# SparkFun_Transceiver_Breakout_NRF24LU1.net
KiCad netlist of a schematic drawn in EAGLE
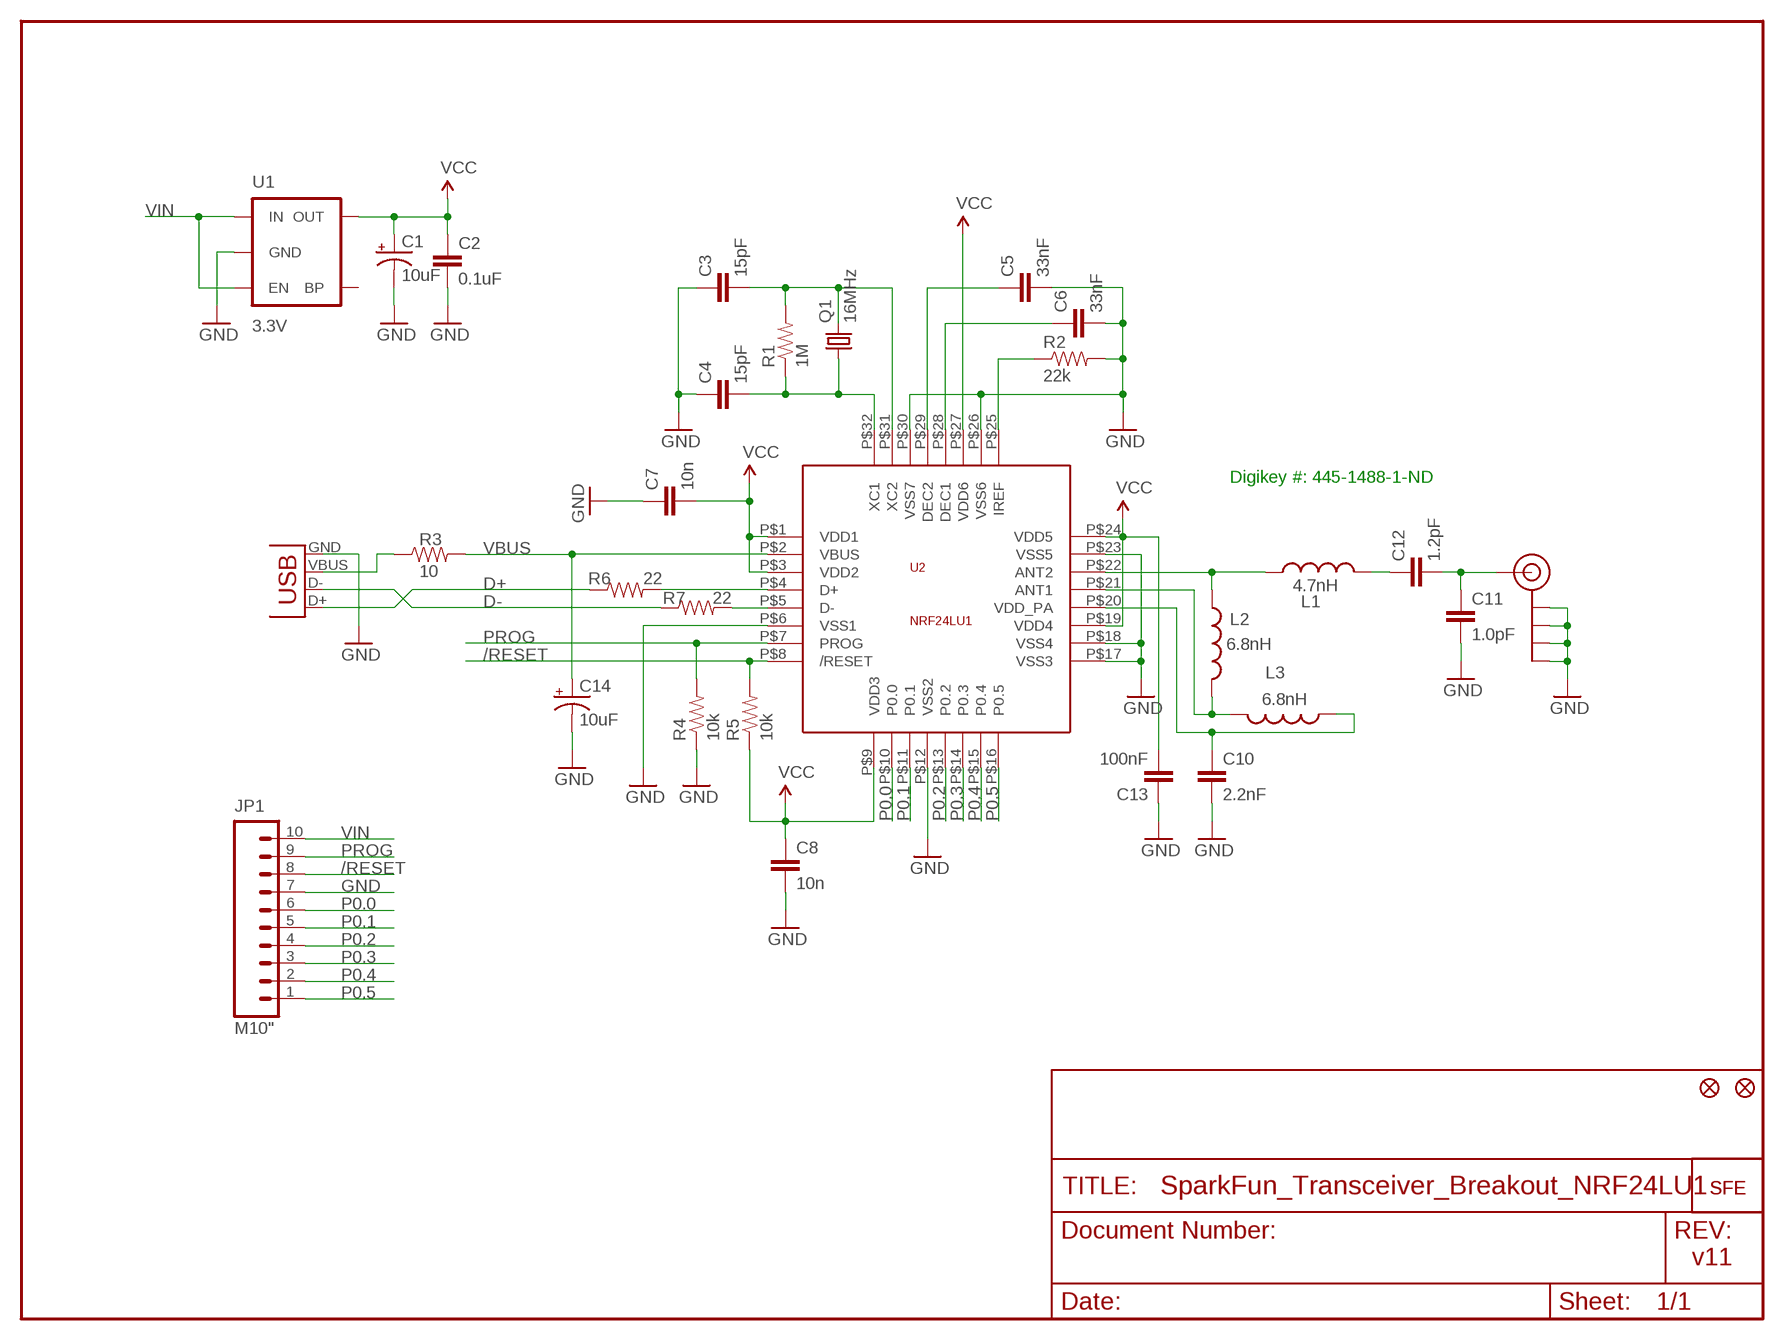
[diagram p0: schematic, sheet 1]

(export (version "E")
  (design (tool "Eeschema 10.0.6"))
  (components
    (comp (ref "C1")
      (value "10uF")
      (footprint "eagle-import:EIA3216")
      (libsource (lib "eagle-import") (part "CAP_POL1206"))
    )
    (comp (ref "C2")
      (value "0.1uF")
      (footprint "eagle-import:0402-CAP")
      (libsource (lib "eagle-import") (part "CAP0402-CAP"))
    )
    (comp (ref "C3")
      (value "15pF")
      (footprint "eagle-import:0402-CAP")
      (libsource (lib "eagle-import") (part "CAP0402-CAP"))
    )
    (comp (ref "C4")
      (value "15pF")
      (footprint "eagle-import:0402-CAP")
      (libsource (lib "eagle-import") (part "CAP0402-CAP"))
    )
    (comp (ref "C5")
      (value "33nF")
      (footprint "eagle-import:0402-CAP")
      (libsource (lib "eagle-import") (part "CAP0402-CAP"))
    )
    (comp (ref "C6")
      (value "33nF")
      (footprint "eagle-import:0402-CAP")
      (libsource (lib "eagle-import") (part "CAP0402-CAP"))
    )
    (comp (ref "C7")
      (value "10n")
      (footprint "eagle-import:0402-CAP")
      (libsource (lib "eagle-import") (part "CAP0402-CAP"))
    )
    (comp (ref "C8")
      (value "10n")
      (footprint "eagle-import:0402-CAP")
      (libsource (lib "eagle-import") (part "CAP0402-CAP"))
    )
    (comp (ref "C10")
      (value "2.2nF")
      (footprint "eagle-import:0402-CAP")
      (libsource (lib "eagle-import") (part "CAP0402-CAP"))
    )
    (comp (ref "C11")
      (value "1.0pF")
      (footprint "eagle-import:0402-CAP")
      (libsource (lib "eagle-import") (part "CAP0402-CAP"))
    )
    (comp (ref "C12")
      (value "1.2pF")
      (footprint "eagle-import:0402-CAP")
      (libsource (lib "eagle-import") (part "CAP0402-CAP"))
    )
    (comp (ref "C13")
      (value "100nF")
      (footprint "eagle-import:0402-CAP")
      (libsource (lib "eagle-import") (part "CAP0402-CAP"))
    )
    (comp (ref "C14")
      (value "10uF")
      (footprint "eagle-import:EIA3216")
      (libsource (lib "eagle-import") (part "CAP_POL1206"))
    )
    (comp (ref "J$1")
      (value "SMA_EDGE")
      (footprint "eagle-import:SMA-EDGE")
      (libsource (lib "eagle-import") (part "SMA_EDGE"))
    )
    (comp (ref "JP1")
      (value "M10\"")
      (footprint "eagle-import:1X10")
      (libsource (lib "eagle-import") (part "M10{dblquote}"))
    )
    (comp (ref "JP2")
      (value "LOGO-SFENEW")
      (footprint "eagle-import:SFE-NEW-WEBLOGO")
      (libsource (lib "eagle-import") (part "LOGO-SFENEW"))
    )
    (comp (ref "L1")
      (value "4.7nH")
      (footprint "eagle-import:C0402")
      (libsource (lib "eagle-import") (part "INDUCTOR0402"))
    )
    (comp (ref "L2")
      (value "6.8nH")
      (footprint "eagle-import:C0402")
      (libsource (lib "eagle-import") (part "INDUCTOR0402"))
    )
    (comp (ref "L3")
      (value "6.8nH")
      (footprint "eagle-import:C0402")
      (libsource (lib "eagle-import") (part "INDUCTOR0402"))
    )
    (comp (ref "Q1")
      (value "16MHz")
      (footprint "eagle-import:CRYSTAL-SMD-5X3")
      (libsource (lib "eagle-import") (part "CRYSTAL5X3"))
    )
    (comp (ref "R1")
      (value "1M")
      (footprint "eagle-import:0402-RES")
      (libsource (lib "eagle-import") (part "RESISTOR0402-RES"))
    )
    (comp (ref "R2")
      (value "22k")
      (footprint "eagle-import:0402-RES")
      (libsource (lib "eagle-import") (part "RESISTOR0402-RES"))
    )
    (comp (ref "R3")
      (value "10")
      (footprint "eagle-import:1206")
      (libsource (lib "eagle-import") (part "RESISTOR1206"))
    )
    (comp (ref "R4")
      (value "10k")
      (footprint "eagle-import:0402-RES")
      (libsource (lib "eagle-import") (part "RESISTOR0402-RES"))
    )
    (comp (ref "R5")
      (value "10k")
      (footprint "eagle-import:0402-RES")
      (libsource (lib "eagle-import") (part "RESISTOR0402-RES"))
    )
    (comp (ref "R6")
      (value "22")
      (footprint "eagle-import:0402-RES")
      (libsource (lib "eagle-import") (part "RESISTOR0402-RES"))
    )
    (comp (ref "R7")
      (value "22")
      (footprint "eagle-import:0402-RES")
      (libsource (lib "eagle-import") (part "RESISTOR0402-RES"))
    )
    (comp (ref "U$12")
      (value "FIDUCIAL1X2")
      (footprint "eagle-import:FIDUCIAL-1X2")
      (libsource (lib "eagle-import") (part "FIDUCIAL1X2"))
    )
    (comp (ref "U$13")
      (value "FIDUCIAL1X2")
      (footprint "eagle-import:FIDUCIAL-1X2")
      (libsource (lib "eagle-import") (part "FIDUCIAL1X2"))
    )
    (comp (ref "U$14")
      (value "LOGO-SFESK")
      (footprint "eagle-import:SFE-LOGO-FLAME")
      (libsource (lib "eagle-import") (part "LOGO-SFESK"))
    )
    (comp (ref "U1")
      (value "3.3V")
      (footprint "eagle-import:SOT23-5")
      (libsource (lib "eagle-import") (part "V_REG_LDOSMD"))
    )
    (comp (ref "U2")
      (value "NRF24LU1")
      (footprint "eagle-import:QFN-32")
      (libsource (lib "eagle-import") (part "NRF24LU1"))
    )
    (comp (ref "X1")
      (value "USBSMD")
      (footprint "eagle-import:USB-MINIB")
      (libsource (lib "eagle-import") (part "USBSMD"))
    )
  )
  (nets
    (net (code "1") (name "/D+") (class "Default")
      (node (ref "R6") (pin "1") (pinfunction "1_1") (pintype "passive"))
      (node (ref "X1") (pin "D+") (pinfunction "D+_D+") (pintype "bidirectional"))
    )
    (net (code "2") (name "/D-") (class "Default")
      (node (ref "R7") (pin "1") (pinfunction "1_1") (pintype "passive"))
      (node (ref "X1") (pin "D-") (pinfunction "D-_D-") (pintype "bidirectional"))
    )
    (net (code "3") (name "/P0.0") (class "Default")
      (node (ref "JP1") (pin "6") (pinfunction "6_6") (pintype "passive"))
      (node (ref "U2") (pin "P$10") (pinfunction "P0.0_P$10") (pintype "bidirectional"))
    )
    (net (code "4") (name "/P0.1") (class "Default")
      (node (ref "JP1") (pin "5") (pinfunction "5_5") (pintype "passive"))
      (node (ref "U2") (pin "P$11") (pinfunction "P0.1_P$11") (pintype "bidirectional"))
    )
    (net (code "5") (name "/P0.2") (class "Default")
      (node (ref "JP1") (pin "4") (pinfunction "4_4") (pintype "passive"))
      (node (ref "U2") (pin "P$13") (pinfunction "P0.2_P$13") (pintype "bidirectional"))
    )
    (net (code "6") (name "/P0.3") (class "Default")
      (node (ref "JP1") (pin "3") (pinfunction "3_3") (pintype "passive"))
      (node (ref "U2") (pin "P$14") (pinfunction "P0.3_P$14") (pintype "bidirectional"))
    )
    (net (code "7") (name "/P0.4") (class "Default")
      (node (ref "JP1") (pin "2") (pinfunction "2_2") (pintype "passive"))
      (node (ref "U2") (pin "P$15") (pinfunction "P0.4_P$15") (pintype "bidirectional"))
    )
    (net (code "8") (name "/P0.5") (class "Default")
      (node (ref "JP1") (pin "1") (pinfunction "1_1") (pintype "passive"))
      (node (ref "U2") (pin "P$16") (pinfunction "P0.5_P$16") (pintype "bidirectional"))
    )
    (net (code "9") (name "/PROG") (class "Default")
      (node (ref "JP1") (pin "9") (pinfunction "9_9") (pintype "passive"))
      (node (ref "R4") (pin "2") (pinfunction "2_2") (pintype "passive"))
      (node (ref "U2") (pin "P$7") (pinfunction "PROG_P$7") (pintype "bidirectional"))
    )
    (net (code "10") (name "/VBUS") (class "Default")
      (node (ref "C14") (pin "A") (pinfunction "+_A") (pintype "passive"))
      (node (ref "R3") (pin "2") (pinfunction "2_2") (pintype "passive"))
      (node (ref "U2") (pin "P$2") (pinfunction "VBUS_P$2") (pintype "bidirectional"))
    )
    (net (code "11") (name "/VIN") (class "Default")
      (node (ref "JP1") (pin "10") (pinfunction "10_10") (pintype "passive"))
      (node (ref "U1") (pin "1") (pinfunction "IN_1") (pintype "input"))
      (node (ref "U1") (pin "3") (pinfunction "EN_3") (pintype "input"))
    )
    (net (code "12") (name "/{slash}RESET") (class "Default")
      (node (ref "JP1") (pin "8") (pinfunction "8_8") (pintype "passive"))
      (node (ref "R5") (pin "2") (pinfunction "2_2") (pintype "passive"))
      (node (ref "U2") (pin "P$8") (pinfunction "/RESET_P$8") (pintype "bidirectional"))
    )
    (net (code "13") (name "GND") (class "Default")
      (node (ref "C1") (pin "C") (pinfunction "-_C") (pintype "passive"))
      (node (ref "C10") (pin "2") (pinfunction "2_2") (pintype "passive"))
      (node (ref "C11") (pin "2") (pinfunction "2_2") (pintype "passive"))
      (node (ref "C13") (pin "1") (pinfunction "1_1") (pintype "passive"))
      (node (ref "C14") (pin "C") (pinfunction "-_C") (pintype "passive"))
      (node (ref "C2") (pin "2") (pinfunction "2_2") (pintype "passive"))
      (node (ref "C3") (pin "1") (pinfunction "1_1") (pintype "passive"))
      (node (ref "C4") (pin "1") (pinfunction "1_1") (pintype "passive"))
      (node (ref "C5") (pin "2") (pinfunction "2_2") (pintype "passive"))
      (node (ref "C6") (pin "2") (pinfunction "2_2") (pintype "passive"))
      (node (ref "C7") (pin "1") (pinfunction "1_1") (pintype "passive"))
      (node (ref "C8") (pin "2") (pinfunction "2_2") (pintype "passive"))
      (node (ref "J$1") (pin "GND@0") (pinfunction "GND_GND@0") (pintype "bidirectional"))
      (node (ref "J$1") (pin "GND@1") (pinfunction "GND_GND@1") (pintype "bidirectional"))
      (node (ref "J$1") (pin "GND@2") (pinfunction "GND_GND@2") (pintype "bidirectional"))
      (node (ref "J$1") (pin "GND@3") (pinfunction "GND_GND@3") (pintype "bidirectional"))
      (node (ref "JP1") (pin "7") (pinfunction "7_7") (pintype "passive"))
      (node (ref "R2") (pin "2") (pinfunction "2_2") (pintype "passive"))
      (node (ref "R4") (pin "1") (pinfunction "1_1") (pintype "passive"))
      (node (ref "U1") (pin "2") (pinfunction "GND_2") (pintype "input"))
      (node (ref "U2") (pin "P$12") (pinfunction "VSS2_P$12") (pintype "bidirectional"))
      (node (ref "U2") (pin "P$17") (pinfunction "VSS3_P$17") (pintype "bidirectional"))
      (node (ref "U2") (pin "P$18") (pinfunction "VSS4_P$18") (pintype "bidirectional"))
      (node (ref "U2") (pin "P$23") (pinfunction "VSS5_P$23") (pintype "bidirectional"))
      (node (ref "U2") (pin "P$26") (pinfunction "VSS6_P$26") (pintype "bidirectional"))
      (node (ref "U2") (pin "P$30") (pinfunction "VSS7_P$30") (pintype "bidirectional"))
      (node (ref "U2") (pin "P$6") (pinfunction "VSS1_P$6") (pintype "bidirectional"))
      (node (ref "X1") (pin "GND") (pinfunction "GND_GND") (pintype "bidirectional"))
    )
    (net (code "14") (name "Net-(C12-Pad1)") (class "Default")
      (node (ref "C12") (pin "1") (pinfunction "1_1") (pintype "passive"))
      (node (ref "L1") (pin "2") (pinfunction "2_2") (pintype "passive"))
    )
    (net (code "15") (name "Net-(J$1-SIGNAL)") (class "Default")
      (node (ref "C11") (pin "1") (pinfunction "1_1") (pintype "passive"))
      (node (ref "C12") (pin "2") (pinfunction "2_2") (pintype "passive"))
      (node (ref "J$1") (pin "SIG") (pinfunction "SIGNAL_SIG") (pintype "bidirectional"))
    )
    (net (code "16") (name "Net-(Q1-2)") (class "Default")
      (node (ref "C3") (pin "2") (pinfunction "2_2") (pintype "passive"))
      (node (ref "Q1") (pin "3") (pinfunction "2_3") (pintype "passive"))
      (node (ref "R1") (pin "2") (pinfunction "2_2") (pintype "passive"))
      (node (ref "U2") (pin "P$31") (pinfunction "XC2_P$31") (pintype "bidirectional"))
    )
    (net (code "17") (name "Net-(R3-Pad1)") (class "Default")
      (node (ref "R3") (pin "1") (pinfunction "1_1") (pintype "passive"))
      (node (ref "X1") (pin "VBUS") (pinfunction "VBUS_VBUS") (pintype "bidirectional"))
    )
    (net (code "18") (name "Net-(U2-ANT1)") (class "Default")
      (node (ref "L2") (pin "2") (pinfunction "2_2") (pintype "passive"))
      (node (ref "L3") (pin "2") (pinfunction "2_2") (pintype "passive"))
      (node (ref "U2") (pin "P$21") (pinfunction "ANT1_P$21") (pintype "bidirectional"))
    )
    (net (code "19") (name "Net-(U2-ANT2)") (class "Default")
      (node (ref "L1") (pin "1") (pinfunction "1_1") (pintype "passive"))
      (node (ref "L2") (pin "1") (pinfunction "1_1") (pintype "passive"))
      (node (ref "U2") (pin "P$22") (pinfunction "ANT2_P$22") (pintype "bidirectional"))
    )
    (net (code "20") (name "Net-(U2-D+)") (class "Default")
      (node (ref "R6") (pin "2") (pinfunction "2_2") (pintype "passive"))
      (node (ref "U2") (pin "P$4") (pinfunction "D+_P$4") (pintype "bidirectional"))
    )
    (net (code "21") (name "Net-(U2-D-)") (class "Default")
      (node (ref "R7") (pin "2") (pinfunction "2_2") (pintype "passive"))
      (node (ref "U2") (pin "P$5") (pinfunction "D-_P$5") (pintype "bidirectional"))
    )
    (net (code "22") (name "Net-(U2-DEC1)") (class "Default")
      (node (ref "C6") (pin "1") (pinfunction "1_1") (pintype "passive"))
      (node (ref "U2") (pin "P$28") (pinfunction "DEC1_P$28") (pintype "bidirectional"))
    )
    (net (code "23") (name "Net-(U2-DEC2)") (class "Default")
      (node (ref "C5") (pin "1") (pinfunction "1_1") (pintype "passive"))
      (node (ref "U2") (pin "P$29") (pinfunction "DEC2_P$29") (pintype "bidirectional"))
    )
    (net (code "24") (name "Net-(U2-IREF)") (class "Default")
      (node (ref "R2") (pin "1") (pinfunction "1_1") (pintype "passive"))
      (node (ref "U2") (pin "P$25") (pinfunction "IREF_P$25") (pintype "bidirectional"))
    )
    (net (code "25") (name "Net-(U2-VDD_PA)") (class "Default")
      (node (ref "C10") (pin "1") (pinfunction "1_1") (pintype "passive"))
      (node (ref "L3") (pin "1") (pinfunction "1_1") (pintype "passive"))
      (node (ref "U2") (pin "P$20") (pinfunction "VDD_PA_P$20") (pintype "bidirectional"))
    )
    (net (code "26") (name "Net-(U2-XC1)") (class "Default")
      (node (ref "C4") (pin "2") (pinfunction "2_2") (pintype "passive"))
      (node (ref "Q1") (pin "1") (pinfunction "1_1") (pintype "passive"))
      (node (ref "R1") (pin "1") (pinfunction "1_1") (pintype "passive"))
      (node (ref "U2") (pin "P$32") (pinfunction "XC1_P$32") (pintype "bidirectional"))
    )
    (net (code "27") (name "VCC") (class "Default")
      (node (ref "C1") (pin "A") (pinfunction "+_A") (pintype "passive"))
      (node (ref "C13") (pin "2") (pinfunction "2_2") (pintype "passive"))
      (node (ref "C2") (pin "1") (pinfunction "1_1") (pintype "passive"))
      (node (ref "C7") (pin "2") (pinfunction "2_2") (pintype "passive"))
      (node (ref "C8") (pin "1") (pinfunction "1_1") (pintype "passive"))
      (node (ref "R5") (pin "1") (pinfunction "1_1") (pintype "passive"))
      (node (ref "U1") (pin "5") (pinfunction "OUT_5") (pintype "passive"))
      (node (ref "U2") (pin "P$1") (pinfunction "VDD1_P$1") (pintype "bidirectional"))
      (node (ref "U2") (pin "P$19") (pinfunction "VDD4_P$19") (pintype "bidirectional"))
      (node (ref "U2") (pin "P$24") (pinfunction "VDD5_P$24") (pintype "bidirectional"))
      (node (ref "U2") (pin "P$27") (pinfunction "VDD6_P$27") (pintype "bidirectional"))
      (node (ref "U2") (pin "P$3") (pinfunction "VDD2_P$3") (pintype "bidirectional"))
      (node (ref "U2") (pin "P$9") (pinfunction "VDD3_P$9") (pintype "bidirectional"))
    )
    (net (code "28") (name "unconnected-(U1-BP-Pad4)") (class "Default")
      (node (ref "U1") (pin "4") (pinfunction "BP_4") (pintype "input"))
    )
  )
)
